# USB_OTG.net
KiCad netlist of a schematic drawn in Altium Designer
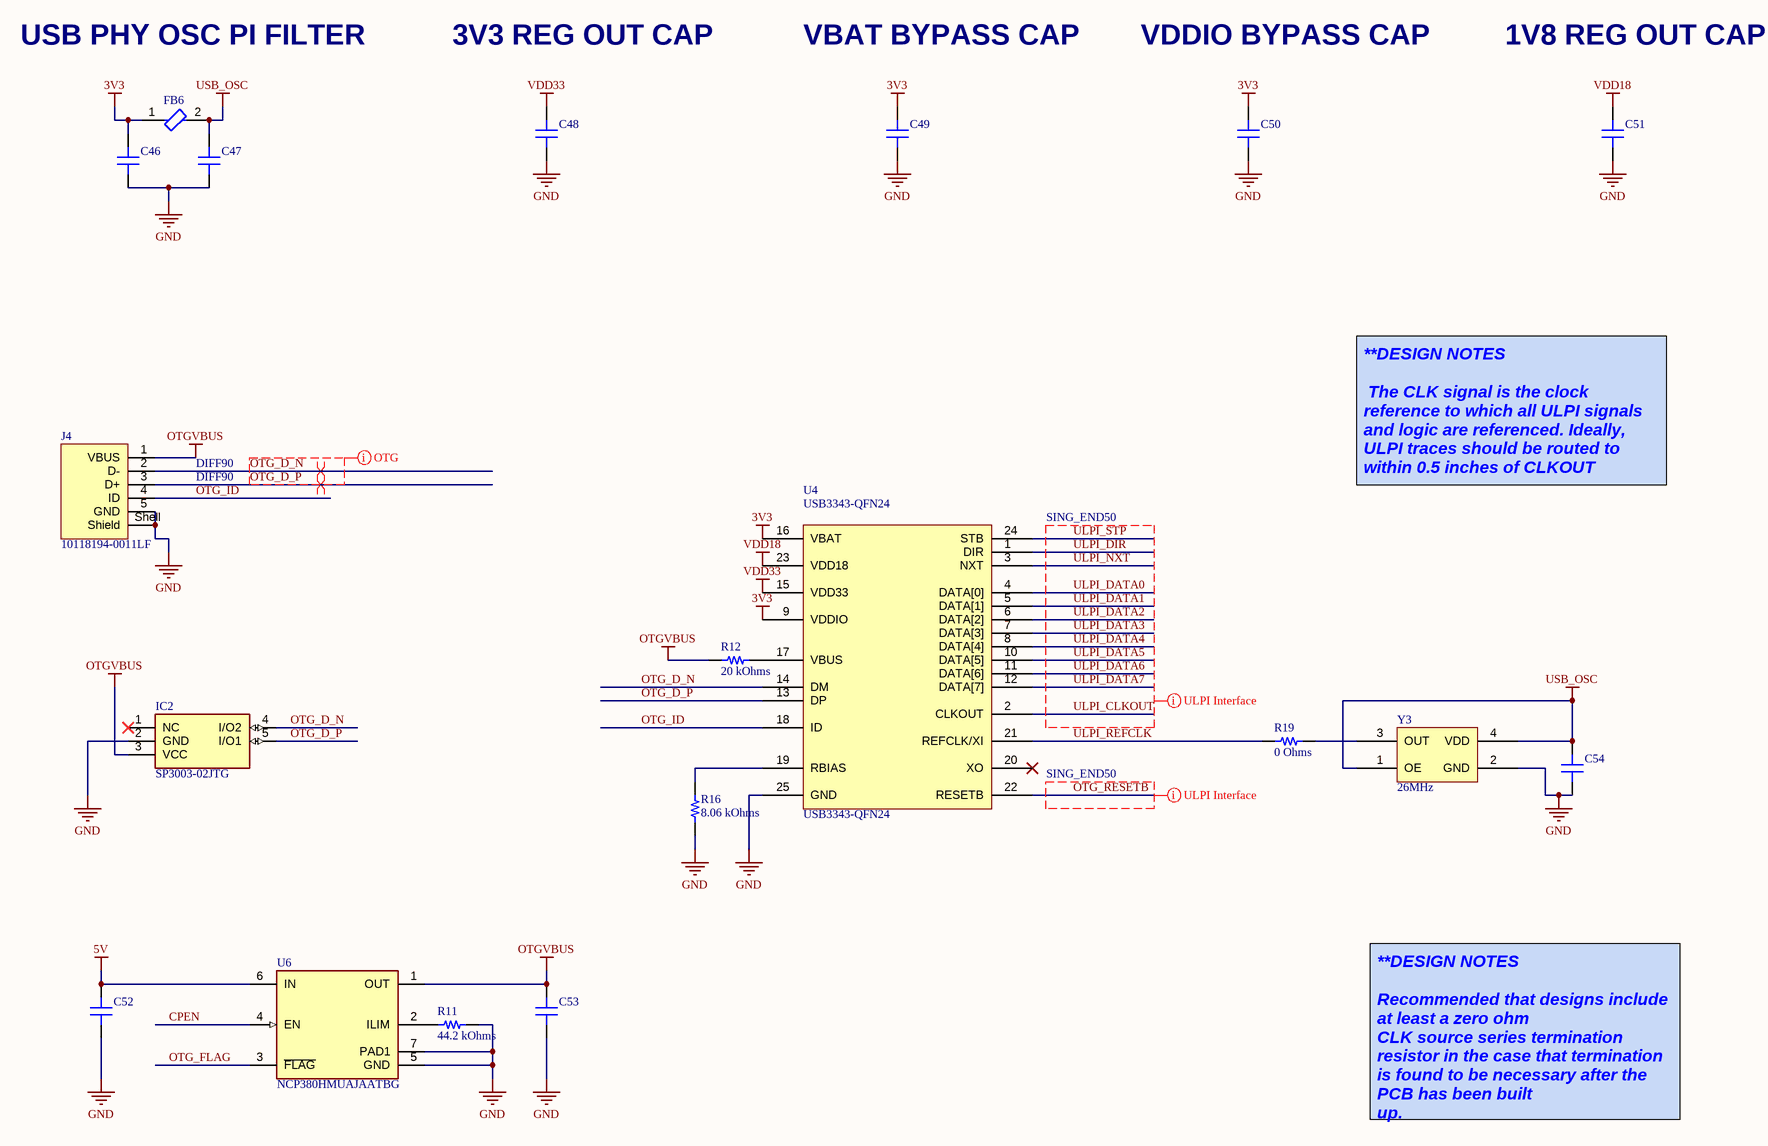
[diagram p0: USB_OTG.SchDoc]

(export (version "E")
  (design (tool "Eeschema 10.0.6"))
  (components
    (comp (ref "C46")
      (value "4.7 µF")
      (footprint "CAP 0402_1005")
      (description "CAP CER 4.7UF 10V X5R 0402")
      (fields
        (field (name "PART NUMBER") "CL05A475MP5NRNC")
        (field (name "MANUFACTURER") "Samsung Electro-Mechanics")
      )
      (libsource (lib "Celestial Altium Library - altium_library") (part "Capacitor"))
    )
    (comp (ref "C47")
      (value "4.7 µF")
      (footprint "CAP 0402_1005")
      (description "CAP CER 4.7UF 10V X5R 0402")
      (fields
        (field (name "PART NUMBER") "CL05A475MP5NRNC")
        (field (name "MANUFACTURER") "Samsung Electro-Mechanics")
      )
      (libsource (lib "Celestial Altium Library - altium_library") (part "Capacitor"))
    )
    (comp (ref "C48")
      (value "4.7µF")
      (footprint "CAP 0402_1005")
      (description "CAP CER 4.7UF 16V X5R 0402")
      (fields (field (name "PART NUMBER") "0402YD475MAT2A") (field (name "MANUFACTURER") "AVX Corporation"))
      (libsource (lib "Celestial Altium Library - altium_library") (part "Capacitor"))
    )
    (comp (ref "C49")
      (value "0.1 µF")
      (footprint "CAP 0402_1005")
      (description "CAP CER 0.1UF 10V X7R 0402")
      (fields (field (name "PART NUMBER") "CC0402KRX7R6BB104") (field (name "MANUFACTURER") "Yageo"))
      (libsource (lib "Celestial Altium Library - altium_library") (part "Capacitor"))
    )
    (comp (ref "C50")
      (value "0.1 µF")
      (footprint "CAP 0402_1005")
      (description "CAP CER 0.1UF 10V X7R 0402")
      (fields (field (name "PART NUMBER") "CC0402KRX7R6BB104") (field (name "MANUFACTURER") "Yageo"))
      (libsource (lib "Celestial Altium Library - altium_library") (part "Capacitor"))
    )
    (comp (ref "C51")
      (value "4.7µF")
      (footprint "CAP 0402_1005")
      (description "CAP CER 4.7UF 16V X5R 0402")
      (fields (field (name "PART NUMBER") "0402YD475MAT2A") (field (name "MANUFACTURER") "AVX Corporation"))
      (libsource (lib "Celestial Altium Library - altium_library") (part "Capacitor"))
    )
    (comp (ref "C52")
      (value "10 µF")
      (footprint "CAP 0402_1005")
      (description "CAP CER 10UF 10V X5R 0402")
      (fields
        (field (name "PART NUMBER") "CL05A106MP8NUB8")
        (field (name "MANUFACTURER") "Samsung Electro-Mechanics")
      )
      (libsource (lib "Celestial Altium Library - altium_library") (part "Capacitor"))
    )
    (comp (ref "C53")
      (value "4.7 µF")
      (footprint "CAP 1210_3225 - 1MM")
      (description "CAP CER 4.7UF 35V X5R 1210")
      (fields (field (name "PART NUMBER") "GMK325BJ475MN-T") (field (name "MANUFACTURER") "Taiyo Yuden"))
      (libsource (lib "Celestial Altium Library - altium_library") (part "Capacitor"))
    )
    (comp (ref "C54")
      (value "10000 pF")
      (footprint "CAP 0402_1005")
      (description "CAP CER 0402 10NF 50V X7R 10%")
      (fields (field (name "PART NUMBER") "C0402C103K5RECAUTO") (field (name "MANUFACTURER") "KEMET"))
      (libsource (lib "Celestial Altium Library - altium_library") (part "Capacitor"))
    )
    (comp (ref "FB6")
      (value "BLM15AX601SN1D")
      (footprint "FP-BLM15-0_05-IPC_B")
      (description "Chip Ferrite Bead, 0402, 600Ω @ 100MHz, 0.34Ω, 25%, 500mA")
      (fields (field (name "TOLERANCE") "25%"))
      (libsource (lib "Altium Content Vault") (part "5f30dd21d616792df468990f7003faa"))
    )
    (comp (ref "IC2")
      (value "SP3003-02JTG")
      (footprint "SamacSys:SOT65P220X110-5N")
      (description "Integrated Circuit")
      (fields (field (name "MOUSER PART NUMBER") "576-SP3003-02JTG"))
      (libsource (lib "*") (part "SP3003-02JTG"))
    )
    (comp (ref "J4")
      (value "10118194-0011LF")
      (footprint "10118194-0011LF")
      (description "USB - micro B USB 2.0 Receptacle Connector 5 Position Surface Mount, Right Angle; Through Hole")
      (fields
        (field (name "DIGI-KEY PART NUMBER") "10118194-0011LF-ND")
        (field (name "MANUFACTURER") "Amphenol ICC (FCI)")
      )
      (libsource (lib "T8_devkit_PCB_1") (part "10118194-0011LF"))
    )
    (comp (ref "R11")
      (value "44.2 kOhms")
      (footprint "RES 0402_1005")
      (description "RES 44.2K OHM 1% 1/16W 0402")
      (fields (field (name "PART NUMBER") "RC0402FR-0744K2L") (field (name "MANUFACTURER") "Yageo"))
      (libsource (lib "Celestial Altium Library - altium_library") (part "Resistor"))
    )
    (comp (ref "R12")
      (value "20 kOhms")
      (footprint "RES 0402_1005")
      (description "RES 20K OHM 5% 1/16W 0402")
      (fields (field (name "PART NUMBER") "RC0402JR-0720KL") (field (name "MANUFACTURER") "Yageo"))
      (libsource (lib "Celestial Altium Library - altium_library") (part "Resistor"))
    )
    (comp (ref "R16")
      (value "8.06 kOhms")
      (footprint "RES 0402_1005")
      (description "RES 8.06K OHM 1% 1/16W 0402")
      (fields (field (name "PART NUMBER") "RC0402FR-078K06L") (field (name "MANUFACTURER") "Yageo"))
      (libsource (lib "Celestial Altium Library - altium_library") (part "Resistor"))
    )
    (comp (ref "R19")
      (value "0 Ohms")
      (footprint "RES 0402_1005")
      (description "RES 0 OHM JUMPER 1/16W 0402")
      (fields (field (name "PART NUMBER") "RC0402JR-070RL") (field (name "MANUFACTURER") "Yageo"))
      (libsource (lib "Celestial Altium Library - altium_library") (part "Resistor"))
    )
    (comp (ref "U4")
      (value "USB3343-QFN24")
      (footprint "QFN50P400X400X85_HS-25N")
      (libsource (lib "T8_devkit_PCB") (part "USB3343-QFN24"))
    )
    (comp (ref "U6")
      (value "NCP380HMUAJAATBG")
      (footprint "FP-517AB-MFG")
      (description "IC PWR SWITCH P-CHAN 1:1 6UDFN")
      (fields
        (field (name "OCTOPART") "https://octopart.com/ncp380hmuajaatbg-on+semiconductor-19977070")
        (field (name "MANUFACTURER") "ON Semiconductor")
      )
      (libsource (lib "Altium Content Vault") (part "723a6d5456884fc28e5ecf41c24379e"))
    )
    (comp (ref "Y3")
      (value "26MHz")
      (footprint "ABRACON ASVTX-11")
      (description "XTAL OSC VCTCXO 26.0000MHZ SNWV")
      (fields
        (field (name "PART NUMBER") "ASVTX-11-A-26.000MHZ-T")
        (field (name "MANUFACTURER") "Abracon LLC")
      )
      (libsource (lib "Celestial Altium Library - altium_library") (part "Abracon VCTCXO ASVTX-11"))
    )
  )
  (nets
    (net (code "1") (name "/CPEN") (class "Default")
      (node (ref "U6") (pin "4") (pinfunction "EN_4") (pintype "input"))
    )
    (net (code "2") (name "/OTG_D_N") (class "Default")
      (node (ref "IC2") (pin "4") (pinfunction "I/O2_4") (pintype "bidirectional"))
      (node (ref "J4") (pin "2") (pinfunction "D-_2") (pintype "passive"))
      (node (ref "U4") (pin "14") (pinfunction "DM_14") (pintype "passive"))
    )
    (net (code "3") (name "/OTG_D_P") (class "Default")
      (node (ref "IC2") (pin "5") (pinfunction "I/O1_5") (pintype "bidirectional"))
      (node (ref "J4") (pin "3") (pinfunction "D+_3") (pintype "passive"))
      (node (ref "U4") (pin "13") (pinfunction "DP_13") (pintype "passive"))
    )
    (net (code "4") (name "/OTG_FLAG") (class "Default")
      (node (ref "U6") (pin "3") (pinfunction "~{FLAG}_3") (pintype "open_collector"))
    )
    (net (code "5") (name "/OTG_ID") (class "Default")
      (node (ref "J4") (pin "4") (pinfunction "ID_4") (pintype "passive"))
      (node (ref "U4") (pin "18") (pinfunction "ID_18") (pintype "passive"))
    )
    (net (code "6") (name "/OTG_RESETB") (class "Default")
      (node (ref "U4") (pin "22") (pinfunction "RESETB_22") (pintype "passive"))
    )
    (net (code "7") (name "/ULPI_CLKOUT") (class "Default")
      (node (ref "U4") (pin "2") (pinfunction "CLKOUT_2") (pintype "passive"))
    )
    (net (code "8") (name "/ULPI_DATA0") (class "Default")
      (node (ref "U4") (pin "4") (pinfunction "DATA[0]_4") (pintype "passive"))
    )
    (net (code "9") (name "/ULPI_DATA1") (class "Default")
      (node (ref "U4") (pin "5") (pinfunction "DATA[1]_5") (pintype "passive"))
    )
    (net (code "10") (name "/ULPI_DATA2") (class "Default")
      (node (ref "U4") (pin "6") (pinfunction "DATA[2]_6") (pintype "passive"))
    )
    (net (code "11") (name "/ULPI_DATA3") (class "Default")
      (node (ref "U4") (pin "7") (pinfunction "DATA[3]_7") (pintype "passive"))
    )
    (net (code "12") (name "/ULPI_DATA4") (class "Default")
      (node (ref "U4") (pin "8") (pinfunction "DATA[4]_8") (pintype "passive"))
    )
    (net (code "13") (name "/ULPI_DATA5") (class "Default")
      (node (ref "U4") (pin "10") (pinfunction "DATA[5]_10") (pintype "passive"))
    )
    (net (code "14") (name "/ULPI_DATA6") (class "Default")
      (node (ref "U4") (pin "11") (pinfunction "DATA[6]_11") (pintype "passive"))
    )
    (net (code "15") (name "/ULPI_DATA7") (class "Default")
      (node (ref "U4") (pin "12") (pinfunction "DATA[7]_12") (pintype "passive"))
    )
    (net (code "16") (name "/ULPI_DIR") (class "Default")
      (node (ref "U4") (pin "1") (pinfunction "DIR_1") (pintype "passive"))
    )
    (net (code "17") (name "/ULPI_NXT") (class "Default")
      (node (ref "U4") (pin "3") (pinfunction "NXT_3") (pintype "passive"))
    )
    (net (code "18") (name "/ULPI_REFCLK") (class "Default")
      (node (ref "R19") (pin "1") (pinfunction "1_1") (pintype "passive"))
      (node (ref "U4") (pin "21") (pinfunction "REFCLK/XI_21") (pintype "passive"))
    )
    (net (code "19") (name "/ULPI_STP") (class "Default")
      (node (ref "U4") (pin "24") (pinfunction "STB_24") (pintype "passive"))
    )
    (net (code "20") (name "3V3") (class "Default")
      (node (ref "C46") (pin "2") (pinfunction "2_2") (pintype "passive"))
      (node (ref "C49") (pin "2") (pinfunction "2_2") (pintype "passive"))
      (node (ref "C50") (pin "2") (pinfunction "2_2") (pintype "passive"))
      (node (ref "FB6") (pin "1") (pinfunction "1_1") (pintype "passive"))
      (node (ref "U4") (pin "16") (pinfunction "VBAT_16") (pintype "passive"))
      (node (ref "U4") (pin "9") (pinfunction "VDDIO_9") (pintype "passive"))
    )
    (net (code "21") (name "5V") (class "Default")
      (node (ref "C52") (pin "2") (pinfunction "2_2") (pintype "passive"))
      (node (ref "U6") (pin "6") (pinfunction "IN_6") (pintype "power_in"))
    )
    (net (code "22") (name "GND") (class "Default")
      (node (ref "C46") (pin "1") (pinfunction "1_1") (pintype "passive"))
      (node (ref "C47") (pin "1") (pinfunction "1_1") (pintype "passive"))
      (node (ref "C48") (pin "1") (pinfunction "1_1") (pintype "passive"))
      (node (ref "C49") (pin "1") (pinfunction "1_1") (pintype "passive"))
      (node (ref "C50") (pin "1") (pinfunction "1_1") (pintype "passive"))
      (node (ref "C51") (pin "1") (pinfunction "1_1") (pintype "passive"))
      (node (ref "C52") (pin "1") (pinfunction "1_1") (pintype "passive"))
      (node (ref "C53") (pin "1") (pinfunction "1_1") (pintype "passive"))
      (node (ref "C54") (pin "1") (pinfunction "1_1") (pintype "passive"))
      (node (ref "IC2") (pin "2") (pinfunction "GND_2") (pintype "power_in"))
      (node (ref "J4") (pin "5") (pinfunction "GND_5") (pintype "passive"))
      (node (ref "J4") (pin "Shell") (pinfunction "Shield_Shell") (pintype "passive"))
      (node (ref "R11") (pin "2") (pinfunction "2_2") (pintype "passive"))
      (node (ref "R16") (pin "2") (pinfunction "2_2") (pintype "passive"))
      (node (ref "U4") (pin "25") (pinfunction "GND_25") (pintype "passive"))
      (node (ref "U6") (pin "5") (pinfunction "GND_5") (pintype "power_in"))
      (node (ref "U6") (pin "7") (pinfunction "PAD1_7") (pintype "passive"))
      (node (ref "Y3") (pin "2") (pinfunction "GND_2") (pintype "passive"))
    )
    (net (code "23") (name "Net-(U4-RBIAS)") (class "Default")
      (node (ref "R16") (pin "1") (pinfunction "1_1") (pintype "passive"))
      (node (ref "U4") (pin "19") (pinfunction "RBIAS_19") (pintype "passive"))
    )
    (net (code "24") (name "Net-(U4-VBUS)") (class "Default")
      (node (ref "R12") (pin "2") (pinfunction "2_2") (pintype "passive"))
      (node (ref "U4") (pin "17") (pinfunction "VBUS_17") (pintype "passive"))
    )
    (net (code "25") (name "Net-(U6-ILIM)") (class "Default")
      (node (ref "R11") (pin "1") (pinfunction "1_1") (pintype "passive"))
      (node (ref "U6") (pin "2") (pinfunction "ILIM_2") (pintype "passive"))
    )
    (net (code "26") (name "Net-(Y3-OUT)") (class "Default")
      (node (ref "R19") (pin "2") (pinfunction "2_2") (pintype "passive"))
      (node (ref "Y3") (pin "3") (pinfunction "OUT_3") (pintype "passive"))
    )
    (net (code "27") (name "OTGVBUS") (class "Default")
      (node (ref "C53") (pin "2") (pinfunction "2_2") (pintype "passive"))
      (node (ref "IC2") (pin "3") (pinfunction "VCC_3") (pintype "power_in"))
      (node (ref "J4") (pin "1") (pinfunction "VBUS_1") (pintype "passive"))
      (node (ref "R12") (pin "1") (pinfunction "1_1") (pintype "passive"))
      (node (ref "U6") (pin "1") (pinfunction "OUT_1") (pintype "power_in"))
    )
    (net (code "28") (name "USB_OSC") (class "Default")
      (node (ref "C47") (pin "2") (pinfunction "2_2") (pintype "passive"))
      (node (ref "C54") (pin "2") (pinfunction "2_2") (pintype "passive"))
      (node (ref "FB6") (pin "2") (pinfunction "2_2") (pintype "passive"))
      (node (ref "Y3") (pin "1") (pinfunction "OE_1") (pintype "passive"))
      (node (ref "Y3") (pin "4") (pinfunction "VDD_4") (pintype "passive"))
    )
    (net (code "29") (name "VDD18") (class "Default")
      (node (ref "C51") (pin "2") (pinfunction "2_2") (pintype "passive"))
      (node (ref "U4") (pin "23") (pinfunction "VDD18_23") (pintype "passive"))
    )
    (net (code "30") (name "VDD33") (class "Default")
      (node (ref "C48") (pin "2") (pinfunction "2_2") (pintype "passive"))
      (node (ref "U4") (pin "15") (pinfunction "VDD33_15") (pintype "passive"))
    )
    (net (code "31") (name "unconnected-(IC2-NC-Pad1)") (class "Default")
      (node (ref "IC2") (pin "1") (pinfunction "NC_1") (pintype "passive+no_connect"))
    )
    (net (code "32") (name "unconnected-(U4-XO-Pad20)") (class "Default")
      (node (ref "U4") (pin "20") (pinfunction "XO_20") (pintype "passive+no_connect"))
    )
  )
)
